# TR-02.net
KiCad netlist of a schematic drawn in EAGLE
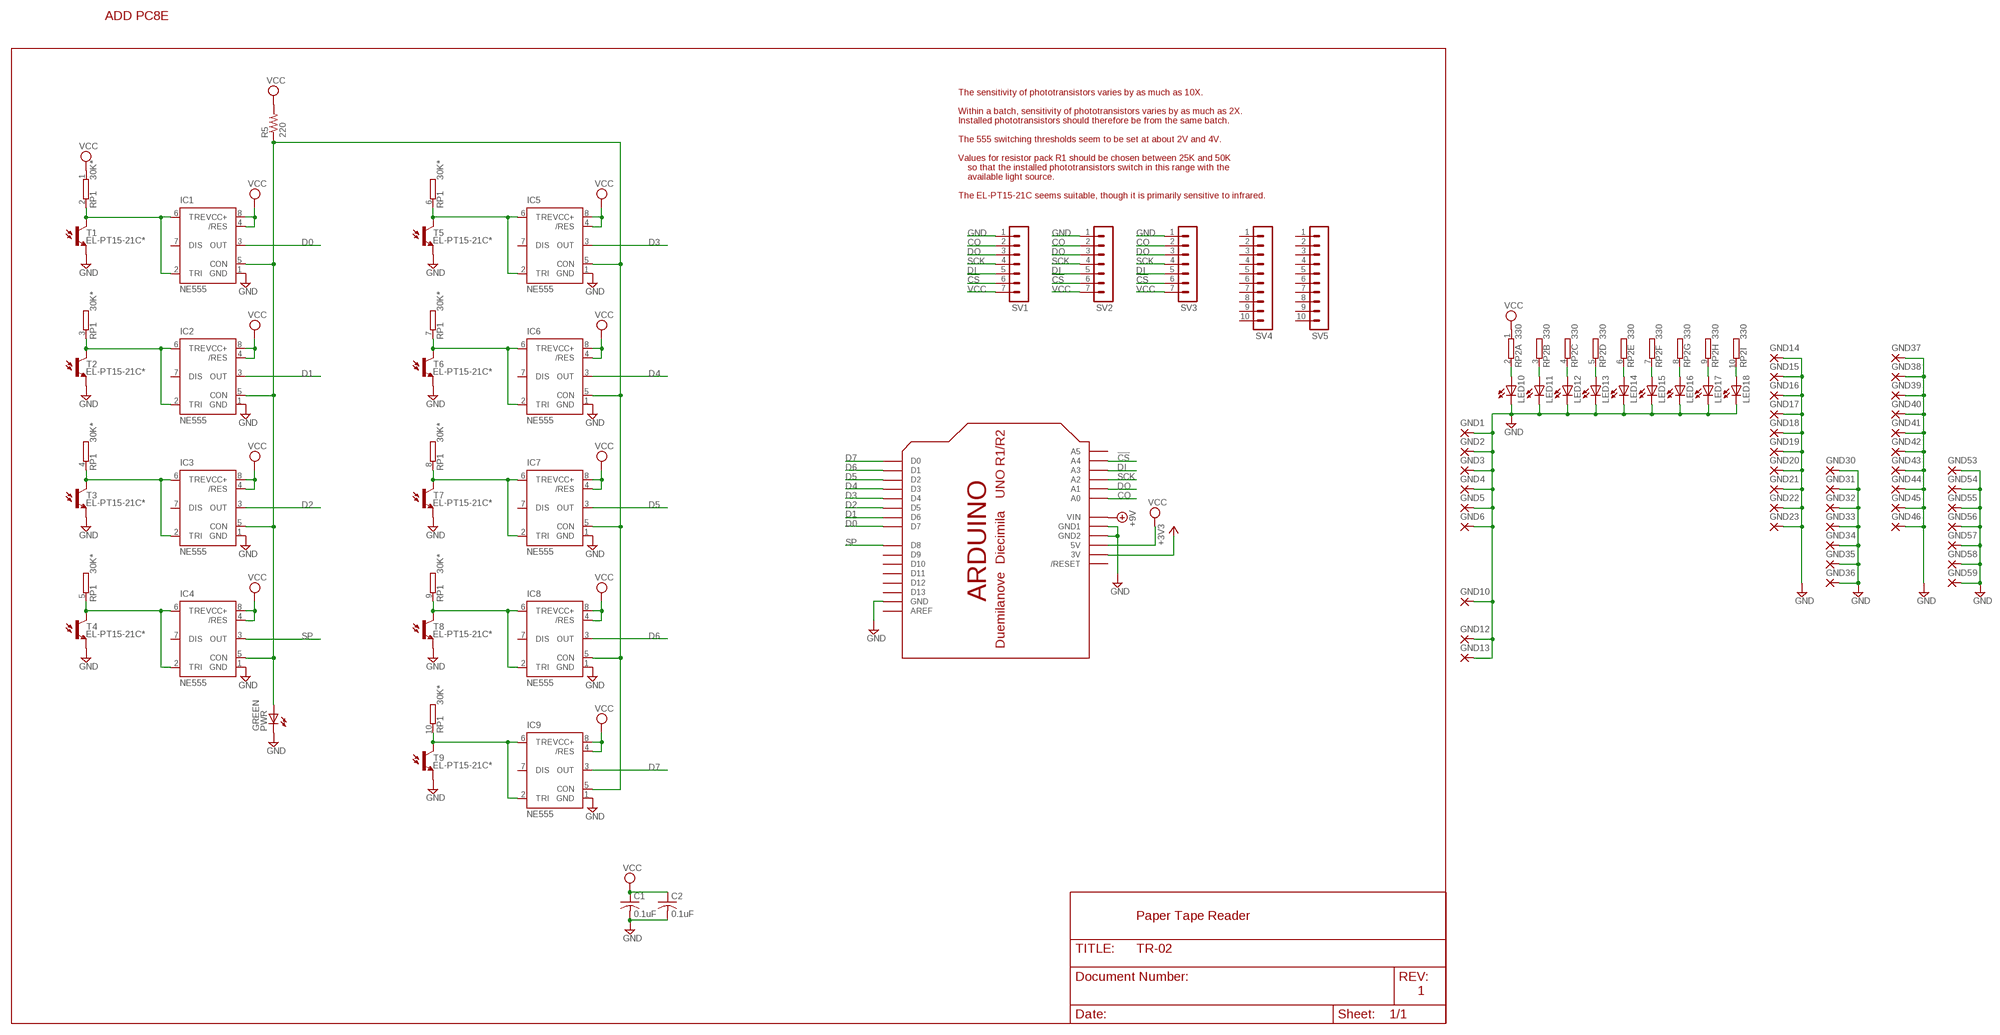
[diagram p0: schematic, sheet 1]

(export (version "E")
  (design (tool "Eeschema 10.0.6"))
  (components
    (comp (ref "C1")
      (value "0.1uF")
      (footprint "eagle-import:C050-030X075")
      (libsource (lib "eagle-import") (part "C-US050-030X075"))
    )
    (comp (ref "C2")
      (value "0.1uF")
      (footprint "eagle-import:C050-030X075")
      (libsource (lib "eagle-import") (part "C-US050-030X075"))
    )
    (comp (ref "GND1")
      (value "2,15/1,0")
      (footprint "eagle-import:2,15_1,0")
      (libsource (lib "eagle-import") (part "2,15/1,0"))
    )
    (comp (ref "GND2")
      (value "2,15/1,0")
      (footprint "eagle-import:2,15_1,0")
      (libsource (lib "eagle-import") (part "2,15/1,0"))
    )
    (comp (ref "GND3")
      (value "2,15/1,0")
      (footprint "eagle-import:2,15_1,0")
      (libsource (lib "eagle-import") (part "2,15/1,0"))
    )
    (comp (ref "GND4")
      (value "2,15/1,0")
      (footprint "eagle-import:2,15_1,0")
      (libsource (lib "eagle-import") (part "2,15/1,0"))
    )
    (comp (ref "GND5")
      (value "2,15/1,0")
      (footprint "eagle-import:2,15_1,0")
      (libsource (lib "eagle-import") (part "2,15/1,0"))
    )
    (comp (ref "GND6")
      (value "2,15/1,0")
      (footprint "eagle-import:2,15_1,0")
      (libsource (lib "eagle-import") (part "2,15/1,0"))
    )
    (comp (ref "GND10")
      (value "2,15/1,0")
      (footprint "eagle-import:2,15_1,0")
      (libsource (lib "eagle-import") (part "2,15/1,0"))
    )
    (comp (ref "GND12")
      (value "2,15/1,0")
      (footprint "eagle-import:2,15_1,0")
      (libsource (lib "eagle-import") (part "2,15/1,0"))
    )
    (comp (ref "GND13")
      (value "2,15/1,0")
      (footprint "eagle-import:2,15_1,0")
      (libsource (lib "eagle-import") (part "2,15/1,0"))
    )
    (comp (ref "GND14")
      (value "2,15/1,0")
      (footprint "eagle-import:2,15_1,0")
      (libsource (lib "eagle-import") (part "2,15/1,0"))
    )
    (comp (ref "GND15")
      (value "2,15/1,0")
      (footprint "eagle-import:2,15_1,0")
      (libsource (lib "eagle-import") (part "2,15/1,0"))
    )
    (comp (ref "GND16")
      (value "2,15/1,0")
      (footprint "eagle-import:2,15_1,0")
      (libsource (lib "eagle-import") (part "2,15/1,0"))
    )
    (comp (ref "GND17")
      (value "2,15/1,0")
      (footprint "eagle-import:2,15_1,0")
      (libsource (lib "eagle-import") (part "2,15/1,0"))
    )
    (comp (ref "GND18")
      (value "2,15/1,0")
      (footprint "eagle-import:2,15_1,0")
      (libsource (lib "eagle-import") (part "2,15/1,0"))
    )
    (comp (ref "GND19")
      (value "2,15/1,0")
      (footprint "eagle-import:2,15_1,0")
      (libsource (lib "eagle-import") (part "2,15/1,0"))
    )
    (comp (ref "GND20")
      (value "2,15/1,0")
      (footprint "eagle-import:2,15_1,0")
      (libsource (lib "eagle-import") (part "2,15/1,0"))
    )
    (comp (ref "GND21")
      (value "2,15/1,0")
      (footprint "eagle-import:2,15_1,0")
      (libsource (lib "eagle-import") (part "2,15/1,0"))
    )
    (comp (ref "GND22")
      (value "2,15/1,0")
      (footprint "eagle-import:2,15_1,0")
      (libsource (lib "eagle-import") (part "2,15/1,0"))
    )
    (comp (ref "GND23")
      (value "2,15/1,0")
      (footprint "eagle-import:2,15_1,0")
      (libsource (lib "eagle-import") (part "2,15/1,0"))
    )
    (comp (ref "GND30")
      (value "2,15/1,0")
      (footprint "eagle-import:2,15_1,0")
      (libsource (lib "eagle-import") (part "2,15/1,0"))
    )
    (comp (ref "GND31")
      (value "2,15/1,0")
      (footprint "eagle-import:2,15_1,0")
      (libsource (lib "eagle-import") (part "2,15/1,0"))
    )
    (comp (ref "GND32")
      (value "2,15/1,0")
      (footprint "eagle-import:2,15_1,0")
      (libsource (lib "eagle-import") (part "2,15/1,0"))
    )
    (comp (ref "GND33")
      (value "2,15/1,0")
      (footprint "eagle-import:2,15_1,0")
      (libsource (lib "eagle-import") (part "2,15/1,0"))
    )
    (comp (ref "GND34")
      (value "2,15/1,0")
      (footprint "eagle-import:2,15_1,0")
      (libsource (lib "eagle-import") (part "2,15/1,0"))
    )
    (comp (ref "GND35")
      (value "2,15/1,0")
      (footprint "eagle-import:2,15_1,0")
      (libsource (lib "eagle-import") (part "2,15/1,0"))
    )
    (comp (ref "GND36")
      (value "2,15/1,0")
      (footprint "eagle-import:2,15_1,0")
      (libsource (lib "eagle-import") (part "2,15/1,0"))
    )
    (comp (ref "GND37")
      (value "2,15/1,0")
      (footprint "eagle-import:2,15_1,0")
      (libsource (lib "eagle-import") (part "2,15/1,0"))
    )
    (comp (ref "GND38")
      (value "2,15/1,0")
      (footprint "eagle-import:2,15_1,0")
      (libsource (lib "eagle-import") (part "2,15/1,0"))
    )
    (comp (ref "GND39")
      (value "2,15/1,0")
      (footprint "eagle-import:2,15_1,0")
      (libsource (lib "eagle-import") (part "2,15/1,0"))
    )
    (comp (ref "GND40")
      (value "2,15/1,0")
      (footprint "eagle-import:2,15_1,0")
      (libsource (lib "eagle-import") (part "2,15/1,0"))
    )
    (comp (ref "GND41")
      (value "2,15/1,0")
      (footprint "eagle-import:2,15_1,0")
      (libsource (lib "eagle-import") (part "2,15/1,0"))
    )
    (comp (ref "GND42")
      (value "2,15/1,0")
      (footprint "eagle-import:2,15_1,0")
      (libsource (lib "eagle-import") (part "2,15/1,0"))
    )
    (comp (ref "GND43")
      (value "2,15/1,0")
      (footprint "eagle-import:2,15_1,0")
      (libsource (lib "eagle-import") (part "2,15/1,0"))
    )
    (comp (ref "GND44")
      (value "2,15/1,0")
      (footprint "eagle-import:2,15_1,0")
      (libsource (lib "eagle-import") (part "2,15/1,0"))
    )
    (comp (ref "GND45")
      (value "2,15/1,0")
      (footprint "eagle-import:2,15_1,0")
      (libsource (lib "eagle-import") (part "2,15/1,0"))
    )
    (comp (ref "GND46")
      (value "2,15/1,0")
      (footprint "eagle-import:2,15_1,0")
      (libsource (lib "eagle-import") (part "2,15/1,0"))
    )
    (comp (ref "GND53")
      (value "2,15/1,0")
      (footprint "eagle-import:2,15_1,0")
      (libsource (lib "eagle-import") (part "2,15/1,0"))
    )
    (comp (ref "GND54")
      (value "2,15/1,0")
      (footprint "eagle-import:2,15_1,0")
      (libsource (lib "eagle-import") (part "2,15/1,0"))
    )
    (comp (ref "GND55")
      (value "2,15/1,0")
      (footprint "eagle-import:2,15_1,0")
      (libsource (lib "eagle-import") (part "2,15/1,0"))
    )
    (comp (ref "GND56")
      (value "2,15/1,0")
      (footprint "eagle-import:2,15_1,0")
      (libsource (lib "eagle-import") (part "2,15/1,0"))
    )
    (comp (ref "GND57")
      (value "2,15/1,0")
      (footprint "eagle-import:2,15_1,0")
      (libsource (lib "eagle-import") (part "2,15/1,0"))
    )
    (comp (ref "GND58")
      (value "2,15/1,0")
      (footprint "eagle-import:2,15_1,0")
      (libsource (lib "eagle-import") (part "2,15/1,0"))
    )
    (comp (ref "GND59")
      (value "2,15/1,0")
      (footprint "eagle-import:2,15_1,0")
      (libsource (lib "eagle-import") (part "2,15/1,0"))
    )
    (comp (ref "IC1")
      (value "NE555")
      (footprint "eagle-import:DIL-08")
      (fields (field (name "MF") "Arrow Electronics") (field (name "MPN") "NE555N"))
      (libsource (lib "eagle-import") (part "NE555"))
    )
    (comp (ref "IC2")
      (value "NE555")
      (footprint "eagle-import:DIL-08")
      (fields (field (name "MF") "Arrow Electronics") (field (name "MPN") "NE555N"))
      (libsource (lib "eagle-import") (part "NE555"))
    )
    (comp (ref "IC3")
      (value "NE555")
      (footprint "eagle-import:DIL-08")
      (fields (field (name "MF") "Arrow Electronics") (field (name "MPN") "NE555N"))
      (libsource (lib "eagle-import") (part "NE555"))
    )
    (comp (ref "IC4")
      (value "NE555")
      (footprint "eagle-import:DIL-08")
      (fields (field (name "MF") "Arrow Electronics") (field (name "MPN") "NE555N"))
      (libsource (lib "eagle-import") (part "NE555"))
    )
    (comp (ref "IC5")
      (value "NE555")
      (footprint "eagle-import:DIL-08")
      (fields (field (name "MF") "Arrow Electronics") (field (name "MPN") "NE555N"))
      (libsource (lib "eagle-import") (part "NE555"))
    )
    (comp (ref "IC6")
      (value "NE555")
      (footprint "eagle-import:DIL-08")
      (fields (field (name "MF") "Arrow Electronics") (field (name "MPN") "NE555N"))
      (libsource (lib "eagle-import") (part "NE555"))
    )
    (comp (ref "IC7")
      (value "NE555")
      (footprint "eagle-import:DIL-08")
      (fields (field (name "MF") "Arrow Electronics") (field (name "MPN") "NE555N"))
      (libsource (lib "eagle-import") (part "NE555"))
    )
    (comp (ref "IC8")
      (value "NE555")
      (footprint "eagle-import:DIL-08")
      (fields (field (name "MF") "Arrow Electronics") (field (name "MPN") "NE555N"))
      (libsource (lib "eagle-import") (part "NE555"))
    )
    (comp (ref "IC9")
      (value "NE555")
      (footprint "eagle-import:DIL-08")
      (fields (field (name "MF") "Arrow Electronics") (field (name "MPN") "NE555N"))
      (libsource (lib "eagle-import") (part "NE555"))
    )
    (comp (ref "LED10")
      (value "LEDCHIPLED_1206")
      (footprint "eagle-import:CHIPLED_1206")
      (libsource (lib "eagle-import") (part "opto_LEDCHIPLED_1206"))
    )
    (comp (ref "LED11")
      (value "LEDCHIPLED_1206")
      (footprint "eagle-import:CHIPLED_1206")
      (libsource (lib "eagle-import") (part "opto_LEDCHIPLED_1206"))
    )
    (comp (ref "LED12")
      (value "LEDCHIPLED_1206")
      (footprint "eagle-import:CHIPLED_1206")
      (libsource (lib "eagle-import") (part "opto_LEDCHIPLED_1206"))
    )
    (comp (ref "LED13")
      (value "LEDCHIPLED_1206")
      (footprint "eagle-import:CHIPLED_1206")
      (libsource (lib "eagle-import") (part "opto_LEDCHIPLED_1206"))
    )
    (comp (ref "LED14")
      (value "LEDCHIPLED_1206")
      (footprint "eagle-import:CHIPLED_1206")
      (libsource (lib "eagle-import") (part "opto_LEDCHIPLED_1206"))
    )
    (comp (ref "LED15")
      (value "LEDCHIPLED_1206")
      (footprint "eagle-import:CHIPLED_1206")
      (libsource (lib "eagle-import") (part "opto_LEDCHIPLED_1206"))
    )
    (comp (ref "LED16")
      (value "LEDCHIPLED_1206")
      (footprint "eagle-import:CHIPLED_1206")
      (libsource (lib "eagle-import") (part "opto_LEDCHIPLED_1206"))
    )
    (comp (ref "LED17")
      (value "LEDCHIPLED_1206")
      (footprint "eagle-import:CHIPLED_1206")
      (libsource (lib "eagle-import") (part "opto_LEDCHIPLED_1206"))
    )
    (comp (ref "LED18")
      (value "LEDCHIPLED_1206")
      (footprint "eagle-import:CHIPLED_1206")
      (libsource (lib "eagle-import") (part "opto_LEDCHIPLED_1206"))
    )
    (comp (ref "PWR")
      (value "GREEN")
      (footprint "eagle-import:LED3MM")
      (libsource (lib "eagle-import") (part "LED3MM"))
    )
    (comp (ref "R5")
      (value "220")
      (footprint "eagle-import:0207_10")
      (libsource (lib "eagle-import") (part "R-US_0207/10"))
    )
    (comp (ref "RP1")
      (value "30K*")
      (footprint "eagle-import:SIL10")
      (libsource (lib "eagle-import") (part "GE09RP"))
    )
    (comp (ref "RP2")
      (value "330")
      (footprint "eagle-import:SIL10")
      (libsource (lib "eagle-import") (part "GE09R"))
    )
    (comp (ref "SV1")
      (value "MA07-1")
      (footprint "eagle-import:MA07-1")
      (libsource (lib "eagle-import") (part "MA07-1"))
    )
    (comp (ref "SV2")
      (value "MA07-1")
      (footprint "eagle-import:MA07-1")
      (libsource (lib "eagle-import") (part "MA07-1"))
    )
    (comp (ref "SV3")
      (value "MA07-1")
      (footprint "eagle-import:MA07-1")
      (libsource (lib "eagle-import") (part "MA07-1"))
    )
    (comp (ref "SV4")
      (value "MA10-1")
      (footprint "eagle-import:MA10-1")
      (libsource (lib "eagle-import") (part "MA10-1"))
    )
    (comp (ref "SV5")
      (value "MA10-1")
      (footprint "eagle-import:MA10-1")
      (libsource (lib "eagle-import") (part "MA10-1"))
    )
    (comp (ref "T1")
      (value "EL-PT15-21C*")
      (footprint "eagle-import:CHIPLED_1206")
      (libsource (lib "eagle-import") (part "PHOTOTRANSISTOR"))
    )
    (comp (ref "T2")
      (value "EL-PT15-21C*")
      (footprint "eagle-import:CHIPLED_1206")
      (libsource (lib "eagle-import") (part "PHOTOTRANSISTOR"))
    )
    (comp (ref "T3")
      (value "EL-PT15-21C*")
      (footprint "eagle-import:CHIPLED_1206")
      (libsource (lib "eagle-import") (part "PHOTOTRANSISTOR"))
    )
    (comp (ref "T4")
      (value "EL-PT15-21C*")
      (footprint "eagle-import:CHIPLED_1206")
      (libsource (lib "eagle-import") (part "PHOTOTRANSISTOR"))
    )
    (comp (ref "T5")
      (value "EL-PT15-21C*")
      (footprint "eagle-import:CHIPLED_1206")
      (libsource (lib "eagle-import") (part "PHOTOTRANSISTOR"))
    )
    (comp (ref "T6")
      (value "EL-PT15-21C*")
      (footprint "eagle-import:CHIPLED_1206")
      (libsource (lib "eagle-import") (part "PHOTOTRANSISTOR"))
    )
    (comp (ref "T7")
      (value "EL-PT15-21C*")
      (footprint "eagle-import:CHIPLED_1206")
      (libsource (lib "eagle-import") (part "PHOTOTRANSISTOR"))
    )
    (comp (ref "T8")
      (value "EL-PT15-21C*")
      (footprint "eagle-import:CHIPLED_1206")
      (libsource (lib "eagle-import") (part "PHOTOTRANSISTOR"))
    )
    (comp (ref "T9")
      (value "EL-PT15-21C*")
      (footprint "eagle-import:CHIPLED_1206")
      (libsource (lib "eagle-import") (part "PHOTOTRANSISTOR"))
    )
    (comp (ref "U$2")
      (value "ARDUINODUE")
      (footprint "eagle-import:ARDUINO_DUE_SHIELD")
      (libsource (lib "eagle-import") (part "ARDUINODUE"))
    )
  )
  (nets
    (net (code "1") (name "+3V3") (class "Default")
      (node (ref "U$2") (pin "3V3") (pinfunction "3V_3V3") (pintype "power_in"))
    )
    (net (code "2") (name "+9V") (class "Default")
      (node (ref "U$2") (pin "VIN") (pinfunction "VIN_VIN") (pintype "power_in"))
    )
    (net (code "3") (name "/CO") (class "Default")
      (node (ref "SV1") (pin "2") (pinfunction "2_2") (pintype "passive"))
      (node (ref "SV2") (pin "2") (pinfunction "2_2") (pintype "passive"))
      (node (ref "SV3") (pin "2") (pinfunction "2_2") (pintype "passive"))
      (node (ref "U$2") (pin "A0") (pinfunction "A0_A0") (pintype "bidirectional"))
    )
    (net (code "4") (name "/D0") (class "Default")
      (node (ref "IC1") (pin "3") (pinfunction "OUT_3") (pintype "output"))
      (node (ref "U$2") (pin "7") (pinfunction "D7_7") (pintype "bidirectional"))
    )
    (net (code "5") (name "/D1") (class "Default")
      (node (ref "IC2") (pin "3") (pinfunction "OUT_3") (pintype "output"))
      (node (ref "U$2") (pin "6") (pinfunction "D6_6") (pintype "bidirectional"))
    )
    (net (code "6") (name "/D2") (class "Default")
      (node (ref "IC3") (pin "3") (pinfunction "OUT_3") (pintype "output"))
      (node (ref "U$2") (pin "5") (pinfunction "D5_5") (pintype "bidirectional"))
    )
    (net (code "7") (name "/D3") (class "Default")
      (node (ref "IC5") (pin "3") (pinfunction "OUT_3") (pintype "output"))
      (node (ref "U$2") (pin "4") (pinfunction "D4_4") (pintype "bidirectional"))
    )
    (net (code "8") (name "/D4") (class "Default")
      (node (ref "IC6") (pin "3") (pinfunction "OUT_3") (pintype "output"))
      (node (ref "U$2") (pin "3") (pinfunction "D3_3") (pintype "bidirectional"))
    )
    (net (code "9") (name "/D5") (class "Default")
      (node (ref "IC7") (pin "3") (pinfunction "OUT_3") (pintype "output"))
      (node (ref "U$2") (pin "2") (pinfunction "D2_2") (pintype "bidirectional"))
    )
    (net (code "10") (name "/D6") (class "Default")
      (node (ref "IC8") (pin "3") (pinfunction "OUT_3") (pintype "output"))
      (node (ref "U$2") (pin "1") (pinfunction "D1_1") (pintype "bidirectional"))
    )
    (net (code "11") (name "/D7") (class "Default")
      (node (ref "IC9") (pin "3") (pinfunction "OUT_3") (pintype "output"))
      (node (ref "U$2") (pin "0") (pinfunction "D0_0") (pintype "bidirectional"))
    )
    (net (code "12") (name "/DI") (class "Default")
      (node (ref "SV1") (pin "5") (pinfunction "5_5") (pintype "passive"))
      (node (ref "SV2") (pin "5") (pinfunction "5_5") (pintype "passive"))
      (node (ref "SV3") (pin "5") (pinfunction "5_5") (pintype "passive"))
      (node (ref "U$2") (pin "A3") (pinfunction "A3_A3") (pintype "bidirectional"))
    )
    (net (code "13") (name "/DO") (class "Default")
      (node (ref "SV1") (pin "3") (pinfunction "3_3") (pintype "passive"))
      (node (ref "SV2") (pin "3") (pinfunction "3_3") (pintype "passive"))
      (node (ref "SV3") (pin "3") (pinfunction "3_3") (pintype "passive"))
      (node (ref "U$2") (pin "A1") (pinfunction "A1_A1") (pintype "bidirectional"))
    )
    (net (code "14") (name "/SCK") (class "Default")
      (node (ref "SV1") (pin "4") (pinfunction "4_4") (pintype "passive"))
      (node (ref "SV2") (pin "4") (pinfunction "4_4") (pintype "passive"))
      (node (ref "SV3") (pin "4") (pinfunction "4_4") (pintype "passive"))
      (node (ref "U$2") (pin "A2") (pinfunction "A2_A2") (pintype "bidirectional"))
    )
    (net (code "15") (name "/SP") (class "Default")
      (node (ref "IC4") (pin "3") (pinfunction "OUT_3") (pintype "output"))
      (node (ref "U$2") (pin "8") (pinfunction "D8_8") (pintype "bidirectional"))
    )
    (net (code "16") (name "/~{CS}") (class "Default")
      (node (ref "SV1") (pin "6") (pinfunction "6_6") (pintype "passive"))
      (node (ref "SV2") (pin "6") (pinfunction "6_6") (pintype "passive"))
      (node (ref "SV3") (pin "6") (pinfunction "6_6") (pintype "passive"))
      (node (ref "U$2") (pin "A4") (pinfunction "A4_A4") (pintype "bidirectional"))
    )
    (net (code "17") (name "GND") (class "Default")
      (node (ref "C1") (pin "2") (pinfunction "2_2") (pintype "passive"))
      (node (ref "C2") (pin "2") (pinfunction "2_2") (pintype "passive"))
      (node (ref "GND1") (pin "1") (pinfunction "P_1") (pintype "passive"))
      (node (ref "GND10") (pin "1") (pinfunction "P_1") (pintype "passive"))
      (node (ref "GND12") (pin "1") (pinfunction "P_1") (pintype "passive"))
      (node (ref "GND13") (pin "1") (pinfunction "P_1") (pintype "passive"))
      (node (ref "GND14") (pin "1") (pinfunction "P_1") (pintype "passive"))
      (node (ref "GND15") (pin "1") (pinfunction "P_1") (pintype "passive"))
      (node (ref "GND16") (pin "1") (pinfunction "P_1") (pintype "passive"))
      (node (ref "GND17") (pin "1") (pinfunction "P_1") (pintype "passive"))
      (node (ref "GND18") (pin "1") (pinfunction "P_1") (pintype "passive"))
      (node (ref "GND19") (pin "1") (pinfunction "P_1") (pintype "passive"))
      (node (ref "GND2") (pin "1") (pinfunction "P_1") (pintype "passive"))
      (node (ref "GND20") (pin "1") (pinfunction "P_1") (pintype "passive"))
      (node (ref "GND21") (pin "1") (pinfunction "P_1") (pintype "passive"))
      (node (ref "GND22") (pin "1") (pinfunction "P_1") (pintype "passive"))
      (node (ref "GND23") (pin "1") (pinfunction "P_1") (pintype "passive"))
      (node (ref "GND3") (pin "1") (pinfunction "P_1") (pintype "passive"))
      (node (ref "GND30") (pin "1") (pinfunction "P_1") (pintype "passive"))
      (node (ref "GND31") (pin "1") (pinfunction "P_1") (pintype "passive"))
      (node (ref "GND32") (pin "1") (pinfunction "P_1") (pintype "passive"))
      (node (ref "GND33") (pin "1") (pinfunction "P_1") (pintype "passive"))
      (node (ref "GND34") (pin "1") (pinfunction "P_1") (pintype "passive"))
      (node (ref "GND35") (pin "1") (pinfunction "P_1") (pintype "passive"))
      (node (ref "GND36") (pin "1") (pinfunction "P_1") (pintype "passive"))
      (node (ref "GND37") (pin "1") (pinfunction "P_1") (pintype "passive"))
      (node (ref "GND38") (pin "1") (pinfunction "P_1") (pintype "passive"))
      (node (ref "GND39") (pin "1") (pinfunction "P_1") (pintype "passive"))
      (node (ref "GND4") (pin "1") (pinfunction "P_1") (pintype "passive"))
      (node (ref "GND40") (pin "1") (pinfunction "P_1") (pintype "passive"))
      (node (ref "GND41") (pin "1") (pinfunction "P_1") (pintype "passive"))
      (node (ref "GND42") (pin "1") (pinfunction "P_1") (pintype "passive"))
      (node (ref "GND43") (pin "1") (pinfunction "P_1") (pintype "passive"))
      (node (ref "GND44") (pin "1") (pinfunction "P_1") (pintype "passive"))
      (node (ref "GND45") (pin "1") (pinfunction "P_1") (pintype "passive"))
      (node (ref "GND46") (pin "1") (pinfunction "P_1") (pintype "passive"))
      (node (ref "GND5") (pin "1") (pinfunction "P_1") (pintype "passive"))
      (node (ref "GND53") (pin "1") (pinfunction "P_1") (pintype "passive"))
      (node (ref "GND54") (pin "1") (pinfunction "P_1") (pintype "passive"))
      (node (ref "GND55") (pin "1") (pinfunction "P_1") (pintype "passive"))
      (node (ref "GND56") (pin "1") (pinfunction "P_1") (pintype "passive"))
      (node (ref "GND57") (pin "1") (pinfunction "P_1") (pintype "passive"))
      (node (ref "GND58") (pin "1") (pinfunction "P_1") (pintype "passive"))
      (node (ref "GND59") (pin "1") (pinfunction "P_1") (pintype "passive"))
      (node (ref "GND6") (pin "1") (pinfunction "P_1") (pintype "passive"))
      (node (ref "IC1") (pin "1") (pinfunction "GND_1") (pintype "power_in"))
      (node (ref "IC2") (pin "1") (pinfunction "GND_1") (pintype "power_in"))
      (node (ref "IC3") (pin "1") (pinfunction "GND_1") (pintype "power_in"))
      (node (ref "IC4") (pin "1") (pinfunction "GND_1") (pintype "power_in"))
      (node (ref "IC5") (pin "1") (pinfunction "GND_1") (pintype "power_in"))
      (node (ref "IC6") (pin "1") (pinfunction "GND_1") (pintype "power_in"))
      (node (ref "IC7") (pin "1") (pinfunction "GND_1") (pintype "power_in"))
      (node (ref "IC8") (pin "1") (pinfunction "GND_1") (pintype "power_in"))
      (node (ref "IC9") (pin "1") (pinfunction "GND_1") (pintype "power_in"))
      (node (ref "LED10") (pin "C") (pinfunction "C_C") (pintype "passive"))
      (node (ref "LED11") (pin "C") (pinfunction "C_C") (pintype "passive"))
      (node (ref "LED12") (pin "C") (pinfunction "C_C") (pintype "passive"))
      (node (ref "LED13") (pin "C") (pinfunction "C_C") (pintype "passive"))
      (node (ref "LED14") (pin "C") (pinfunction "C_C") (pintype "passive"))
      (node (ref "LED15") (pin "C") (pinfunction "C_C") (pintype "passive"))
      (node (ref "LED16") (pin "C") (pinfunction "C_C") (pintype "passive"))
      (node (ref "LED17") (pin "C") (pinfunction "C_C") (pintype "passive"))
      (node (ref "LED18") (pin "C") (pinfunction "C_C") (pintype "passive"))
      (node (ref "PWR") (pin "K") (pinfunction "C_K") (pintype "passive"))
      (node (ref "SV1") (pin "1") (pinfunction "1_1") (pintype "passive"))
      (node (ref "SV2") (pin "1") (pinfunction "1_1") (pintype "passive"))
      (node (ref "SV3") (pin "1") (pinfunction "1_1") (pintype "passive"))
      (node (ref "T1") (pin "C") (pinfunction "E_C") (pintype "passive"))
      (node (ref "T2") (pin "C") (pinfunction "E_C") (pintype "passive"))
      (node (ref "T3") (pin "C") (pinfunction "E_C") (pintype "passive"))
      (node (ref "T4") (pin "C") (pinfunction "E_C") (pintype "passive"))
      (node (ref "T5") (pin "C") (pinfunction "E_C") (pintype "passive"))
      (node (ref "T6") (pin "C") (pinfunction "E_C") (pintype "passive"))
      (node (ref "T7") (pin "C") (pinfunction "E_C") (pintype "passive"))
      (node (ref "T8") (pin "C") (pinfunction "E_C") (pintype "passive"))
      (node (ref "T9") (pin "C") (pinfunction "E_C") (pintype "passive"))
      (node (ref "U$2") (pin "GND") (pinfunction "GND_GND") (pintype "power_in"))
      (node (ref "U$2") (pin "GND_1") (pinfunction "GND1_GND_1") (pintype "power_in"))
      (node (ref "U$2") (pin "GND_2") (pinfunction "GND2_GND_2") (pintype "power_in"))
    )
    (net (code "18") (name "Net-(IC1-CON)") (class "Default")
      (node (ref "IC1") (pin "5") (pinfunction "CON_5") (pintype "input"))
      (node (ref "IC2") (pin "5") (pinfunction "CON_5") (pintype "input"))
      (node (ref "IC3") (pin "5") (pinfunction "CON_5") (pintype "input"))
      (node (ref "IC4") (pin "5") (pinfunction "CON_5") (pintype "input"))
      (node (ref "IC5") (pin "5") (pinfunction "CON_5") (pintype "input"))
      (node (ref "IC6") (pin "5") (pinfunction "CON_5") (pintype "input"))
      (node (ref "IC7") (pin "5") (pinfunction "CON_5") (pintype "input"))
      (node (ref "IC8") (pin "5") (pinfunction "CON_5") (pintype "input"))
      (node (ref "IC9") (pin "5") (pinfunction "CON_5") (pintype "input"))
      (node (ref "PWR") (pin "A") (pinfunction "A_A") (pintype "passive"))
      (node (ref "R5") (pin "1") (pinfunction "1_1") (pintype "passive"))
    )
    (net (code "19") (name "Net-(IC1-TRE)") (class "Default")
      (node (ref "IC1") (pin "2") (pinfunction "TRI_2") (pintype "input"))
      (node (ref "IC1") (pin "6") (pinfunction "TRE_6") (pintype "input"))
      (node (ref "RP1") (pin "2") (pinfunction "2_2") (pintype "passive"))
      (node (ref "T1") (pin "A") (pinfunction "C_A") (pintype "passive"))
    )
    (net (code "20") (name "Net-(IC2-TRE)") (class "Default")
      (node (ref "IC2") (pin "2") (pinfunction "TRI_2") (pintype "input"))
      (node (ref "IC2") (pin "6") (pinfunction "TRE_6") (pintype "input"))
      (node (ref "RP1") (pin "3") (pinfunction "2_3") (pintype "passive"))
      (node (ref "T2") (pin "A") (pinfunction "C_A") (pintype "passive"))
    )
    (net (code "21") (name "Net-(IC3-TRE)") (class "Default")
      (node (ref "IC3") (pin "2") (pinfunction "TRI_2") (pintype "input"))
      (node (ref "IC3") (pin "6") (pinfunction "TRE_6") (pintype "input"))
      (node (ref "RP1") (pin "4") (pinfunction "2_4") (pintype "passive"))
      (node (ref "T3") (pin "A") (pinfunction "C_A") (pintype "passive"))
    )
    (net (code "22") (name "Net-(IC4-TRE)") (class "Default")
      (node (ref "IC4") (pin "2") (pinfunction "TRI_2") (pintype "input"))
      (node (ref "IC4") (pin "6") (pinfunction "TRE_6") (pintype "input"))
      (node (ref "RP1") (pin "5") (pinfunction "2_5") (pintype "passive"))
      (node (ref "T4") (pin "A") (pinfunction "C_A") (pintype "passive"))
    )
    (net (code "23") (name "Net-(IC5-TRE)") (class "Default")
      (node (ref "IC5") (pin "2") (pinfunction "TRI_2") (pintype "input"))
      (node (ref "IC5") (pin "6") (pinfunction "TRE_6") (pintype "input"))
      (node (ref "RP1") (pin "6") (pinfunction "2_6") (pintype "passive"))
      (node (ref "T5") (pin "A") (pinfunction "C_A") (pintype "passive"))
    )
    (net (code "24") (name "Net-(IC6-TRE)") (class "Default")
      (node (ref "IC6") (pin "2") (pinfunction "TRI_2") (pintype "input"))
      (node (ref "IC6") (pin "6") (pinfunction "TRE_6") (pintype "input"))
      (node (ref "RP1") (pin "7") (pinfunction "2_7") (pintype "passive"))
      (node (ref "T6") (pin "A") (pinfunction "C_A") (pintype "passive"))
    )
    (net (code "25") (name "Net-(IC7-TRE)") (class "Default")
      (node (ref "IC7") (pin "2") (pinfunction "TRI_2") (pintype "input"))
      (node (ref "IC7") (pin "6") (pinfunction "TRE_6") (pintype "input"))
      (node (ref "RP1") (pin "8") (pinfunction "2_8") (pintype "passive"))
      (node (ref "T7") (pin "A") (pinfunction "C_A") (pintype "passive"))
    )
    (net (code "26") (name "Net-(IC8-TRE)") (class "Default")
      (node (ref "IC8") (pin "2") (pinfunction "TRI_2") (pintype "input"))
      (node (ref "IC8") (pin "6") (pinfunction "TRE_6") (pintype "input"))
      (node (ref "RP1") (pin "9") (pinfunction "2_9") (pintype "passive"))
      (node (ref "T8") (pin "A") (pinfunction "C_A") (pintype "passive"))
    )
    (net (code "27") (name "Net-(IC9-TRE)") (class "Default")
      (node (ref "IC9") (pin "2") (pinfunction "TRI_2") (pintype "input"))
      (node (ref "IC9") (pin "6") (pinfunction "TRE_6") (pintype "input"))
      (node (ref "RP1") (pin "10") (pinfunction "2_10") (pintype "passive"))
      (node (ref "T9") (pin "A") (pinfunction "C_A") (pintype "passive"))
    )
    (net (code "28") (name "Net-(LED10-PadA)") (class "Default")
      (node (ref "LED10") (pin "A") (pinfunction "A_A") (pintype "passive"))
      (node (ref "RP2") (pin "2") (pinfunction "2_2") (pintype "passive"))
    )
    (net (code "29") (name "Net-(RP2B-2)") (class "Default")
      (node (ref "LED11") (pin "A") (pinfunction "A_A") (pintype "passive"))
      (node (ref "RP2") (pin "3") (pinfunction "2_3") (pintype "passive"))
    )
    (net (code "30") (name "Net-(RP2C-2)") (class "Default")
      (node (ref "LED12") (pin "A") (pinfunction "A_A") (pintype "passive"))
      (node (ref "RP2") (pin "4") (pinfunction "2_4") (pintype "passive"))
    )
    (net (code "31") (name "Net-(RP2D-2)") (class "Default")
      (node (ref "LED13") (pin "A") (pinfunction "A_A") (pintype "passive"))
      (node (ref "RP2") (pin "5") (pinfunction "2_5") (pintype "passive"))
    )
    (net (code "32") (name "Net-(RP2E-2)") (class "Default")
      (node (ref "LED14") (pin "A") (pinfunction "A_A") (pintype "passive"))
      (node (ref "RP2") (pin "6") (pinfunction "2_6") (pintype "passive"))
    )
    (net (code "33") (name "Net-(RP2F-2)") (class "Default")
      (node (ref "LED15") (pin "A") (pinfunction "A_A") (pintype "passive"))
      (node (ref "RP2") (pin "7") (pinfunction "2_7") (pintype "passive"))
    )
    (net (code "34") (name "Net-(RP2G-2)") (class "Default")
      (node (ref "LED16") (pin "A") (pinfunction "A_A") (pintype "passive"))
      (node (ref "RP2") (pin "8") (pinfunction "2_8") (pintype "passive"))
    )
    (net (code "35") (name "Net-(RP2H-2)") (class "Default")
      (node (ref "LED17") (pin "A") (pinfunction "A_A") (pintype "passive"))
      (node (ref "RP2") (pin "9") (pinfunction "2_9") (pintype "passive"))
    )
    (net (code "36") (name "Net-(RP2I-2)") (class "Default")
      (node (ref "LED18") (pin "A") (pinfunction "A_A") (pintype "passive"))
      (node (ref "RP2") (pin "10") (pinfunction "2_10") (pintype "passive"))
    )
    (net (code "37") (name "VCC") (class "Default")
      (node (ref "C1") (pin "1") (pinfunction "1_1") (pintype "passive"))
      (node (ref "C2") (pin "1") (pinfunction "1_1") (pintype "passive"))
      (node (ref "IC1") (pin "4") (pinfunction "/RES_4") (pintype "input"))
      (node (ref "IC1") (pin "8") (pinfunction "VCC+_8") (pintype "power_in"))
      (node (ref "IC2") (pin "4") (pinfunction "/RES_4") (pintype "input"))
      (node (ref "IC2") (pin "8") (pinfunction "VCC+_8") (pintype "power_in"))
      (node (ref "IC3") (pin "4") (pinfunction "/RES_4") (pintype "input"))
      (node (ref "IC3") (pin "8") (pinfunction "VCC+_8") (pintype "power_in"))
      (node (ref "IC4") (pin "4") (pinfunction "/RES_4") (pintype "input"))
      (node (ref "IC4") (pin "8") (pinfunction "VCC+_8") (pintype "power_in"))
      (node (ref "IC5") (pin "4") (pinfunction "/RES_4") (pintype "input"))
      (node (ref "IC5") (pin "8") (pinfunction "VCC+_8") (pintype "power_in"))
      (node (ref "IC6") (pin "4") (pinfunction "/RES_4") (pintype "input"))
      (node (ref "IC6") (pin "8") (pinfunction "VCC+_8") (pintype "power_in"))
      (node (ref "IC7") (pin "4") (pinfunction "/RES_4") (pintype "input"))
      (node (ref "IC7") (pin "8") (pinfunction "VCC+_8") (pintype "power_in"))
      (node (ref "IC8") (pin "4") (pinfunction "/RES_4") (pintype "input"))
      (node (ref "IC8") (pin "8") (pinfunction "VCC+_8") (pintype "power_in"))
      (node (ref "IC9") (pin "4") (pinfunction "/RES_4") (pintype "input"))
      (node (ref "IC9") (pin "8") (pinfunction "VCC+_8") (pintype "power_in"))
      (node (ref "R5") (pin "2") (pinfunction "2_2") (pintype "passive"))
      (node (ref "RP1") (pin "1") (pinfunction "1_1") (pintype "passive"))
      (node (ref "RP2") (pin "1") (pinfunction "1_1") (pintype "passive"))
      (node (ref "SV1") (pin "7") (pinfunction "7_7") (pintype "passive"))
      (node (ref "SV2") (pin "7") (pinfunction "7_7") (pintype "passive"))
      (node (ref "SV3") (pin "7") (pinfunction "7_7") (pintype "passive"))
      (node (ref "U$2") (pin "5V0") (pinfunction "5V_5V0") (pintype "power_in"))
    )
    (net (code "38") (name "unconnected-(IC1-DIS-Pad7)") (class "Default")
      (node (ref "IC1") (pin "7") (pinfunction "DIS_7") (pintype "output"))
    )
    (net (code "39") (name "unconnected-(IC2-DIS-Pad7)") (class "Default")
      (node (ref "IC2") (pin "7") (pinfunction "DIS_7") (pintype "output"))
    )
    (net (code "40") (name "unconnected-(IC3-DIS-Pad7)") (class "Default")
      (node (ref "IC3") (pin "7") (pinfunction "DIS_7") (pintype "output"))
    )
    (net (code "41") (name "unconnected-(IC4-DIS-Pad7)") (class "Default")
      (node (ref "IC4") (pin "7") (pinfunction "DIS_7") (pintype "output"))
    )
    (net (code "42") (name "unconnected-(IC5-DIS-Pad7)") (class "Default")
      (node (ref "IC5") (pin "7") (pinfunction "DIS_7") (pintype "output"))
    )
    (net (code "43") (name "unconnected-(IC6-DIS-Pad7)") (class "Default")
      (node (ref "IC6") (pin "7") (pinfunction "DIS_7") (pintype "output"))
    )
    (net (code "44") (name "unconnected-(IC7-DIS-Pad7)") (class "Default")
      (node (ref "IC7") (pin "7") (pinfunction "DIS_7") (pintype "output"))
    )
    (net (code "45") (name "unconnected-(IC8-DIS-Pad7)") (class "Default")
      (node (ref "IC8") (pin "7") (pinfunction "DIS_7") (pintype "output"))
    )
    (net (code "46") (name "unconnected-(IC9-DIS-Pad7)") (class "Default")
      (node (ref "IC9") (pin "7") (pinfunction "DIS_7") (pintype "output"))
    )
    (net (code "47") (name "unconnected-(SV4-Pad1)") (class "Default")
      (node (ref "SV4") (pin "1") (pinfunction "1_1") (pintype "passive"))
    )
    (net (code "48") (name "unconnected-(SV4-Pad2)") (class "Default")
      (node (ref "SV4") (pin "2") (pinfunction "2_2") (pintype "passive"))
    )
    (net (code "49") (name "unconnected-(SV4-Pad3)") (class "Default")
      (node (ref "SV4") (pin "3") (pinfunction "3_3") (pintype "passive"))
    )
    (net (code "50") (name "unconnected-(SV4-Pad4)") (class "Default")
      (node (ref "SV4") (pin "4") (pinfunction "4_4") (pintype "passive"))
    )
    (net (code "51") (name "unconnected-(SV4-Pad5)") (class "Default")
      (node (ref "SV4") (pin "5") (pinfunction "5_5") (pintype "passive"))
    )
    (net (code "52") (name "unconnected-(SV4-Pad6)") (class "Default")
      (node (ref "SV4") (pin "6") (pinfunction "6_6") (pintype "passive"))
    )
    (net (code "53") (name "unconnected-(SV4-Pad7)") (class "Default")
      (node (ref "SV4") (pin "7") (pinfunction "7_7") (pintype "passive"))
    )
    (net (code "54") (name "unconnected-(SV4-Pad8)") (class "Default")
      (node (ref "SV4") (pin "8") (pinfunction "8_8") (pintype "passive"))
    )
    (net (code "55") (name "unconnected-(SV4-Pad9)") (class "Default")
      (node (ref "SV4") (pin "9") (pinfunction "9_9") (pintype "passive"))
    )
    (net (code "56") (name "unconnected-(SV4-Pad10)") (class "Default")
      (node (ref "SV4") (pin "10") (pinfunction "10_10") (pintype "passive"))
    )
    (net (code "57") (name "unconnected-(SV5-Pad1)") (class "Default")
      (node (ref "SV5") (pin "1") (pinfunction "1_1") (pintype "passive"))
    )
    (net (code "58") (name "unconnected-(SV5-Pad2)") (class "Default")
      (node (ref "SV5") (pin "2") (pinfunction "2_2") (pintype "passive"))
    )
    (net (code "59") (name "unconnected-(SV5-Pad3)") (class "Default")
      (node (ref "SV5") (pin "3") (pinfunction "3_3") (pintype "passive"))
    )
    (net (code "60") (name "unconnected-(SV5-Pad4)") (class "Default")
      (node (ref "SV5") (pin "4") (pinfunction "4_4") (pintype "passive"))
    )
    (net (code "61") (name "unconnected-(SV5-Pad5)") (class "Default")
      (node (ref "SV5") (pin "5") (pinfunction "5_5") (pintype "passive"))
    )
    (net (code "62") (name "unconnected-(SV5-Pad6)") (class "Default")
      (node (ref "SV5") (pin "6") (pinfunction "6_6") (pintype "passive"))
    )
    (net (code "63") (name "unconnected-(SV5-Pad7)") (class "Default")
      (node (ref "SV5") (pin "7") (pinfunction "7_7") (pintype "passive"))
    )
    (net (code "64") (name "unconnected-(SV5-Pad8)") (class "Default")
      (node (ref "SV5") (pin "8") (pinfunction "8_8") (pintype "passive"))
    )
    (net (code "65") (name "unconnected-(SV5-Pad9)") (class "Default")
      (node (ref "SV5") (pin "9") (pinfunction "9_9") (pintype "passive"))
    )
    (net (code "66") (name "unconnected-(SV5-Pad10)") (class "Default")
      (node (ref "SV5") (pin "10") (pinfunction "10_10") (pintype "passive"))
    )
    (net (code "67") (name "unconnected-(U$2-D9-Pad9)") (class "Default")
      (node (ref "U$2") (pin "9") (pinfunction "D9_9") (pintype "bidirectional"))
    )
    (net (code "68") (name "unconnected-(U$2-D10-Pad10)") (class "Default")
      (node (ref "U$2") (pin "10") (pinfunction "D10_10") (pintype "bidirectional"))
    )
    (net (code "69") (name "unconnected-(U$2-D11-Pad11)") (class "Default")
      (node (ref "U$2") (pin "11") (pinfunction "D11_11") (pintype "bidirectional"))
    )
    (net (code "70") (name "unconnected-(U$2-D12-Pad12)") (class "Default")
      (node (ref "U$2") (pin "12") (pinfunction "D12_12") (pintype "bidirectional"))
    )
    (net (code "71") (name "unconnected-(U$2-D13-Pad13)") (class "Default")
      (node (ref "U$2") (pin "13") (pinfunction "D13_13") (pintype "bidirectional"))
    )
    (net (code "72") (name "unconnected-(U$2-PadA5)") (class "Default")
      (node (ref "U$2") (pin "A5") (pinfunction "A5_A5") (pintype "bidirectional"))
    )
    (net (code "73") (name "unconnected-(U$2-PadAREF)") (class "Default")
      (node (ref "U$2") (pin "AREF") (pinfunction "AREF_AREF") (pintype "bidirectional"))
    )
    (net (code "74") (name "unconnected-(U$2-{slash}RESET-PadRESET)") (class "Default")
      (node (ref "U$2") (pin "RESET") (pinfunction "/RESET_RESET") (pintype "bidirectional"))
    )
  )
)
